# Green_Light_Check.net
KiCad netlist of a schematic drawn in Altium Designer
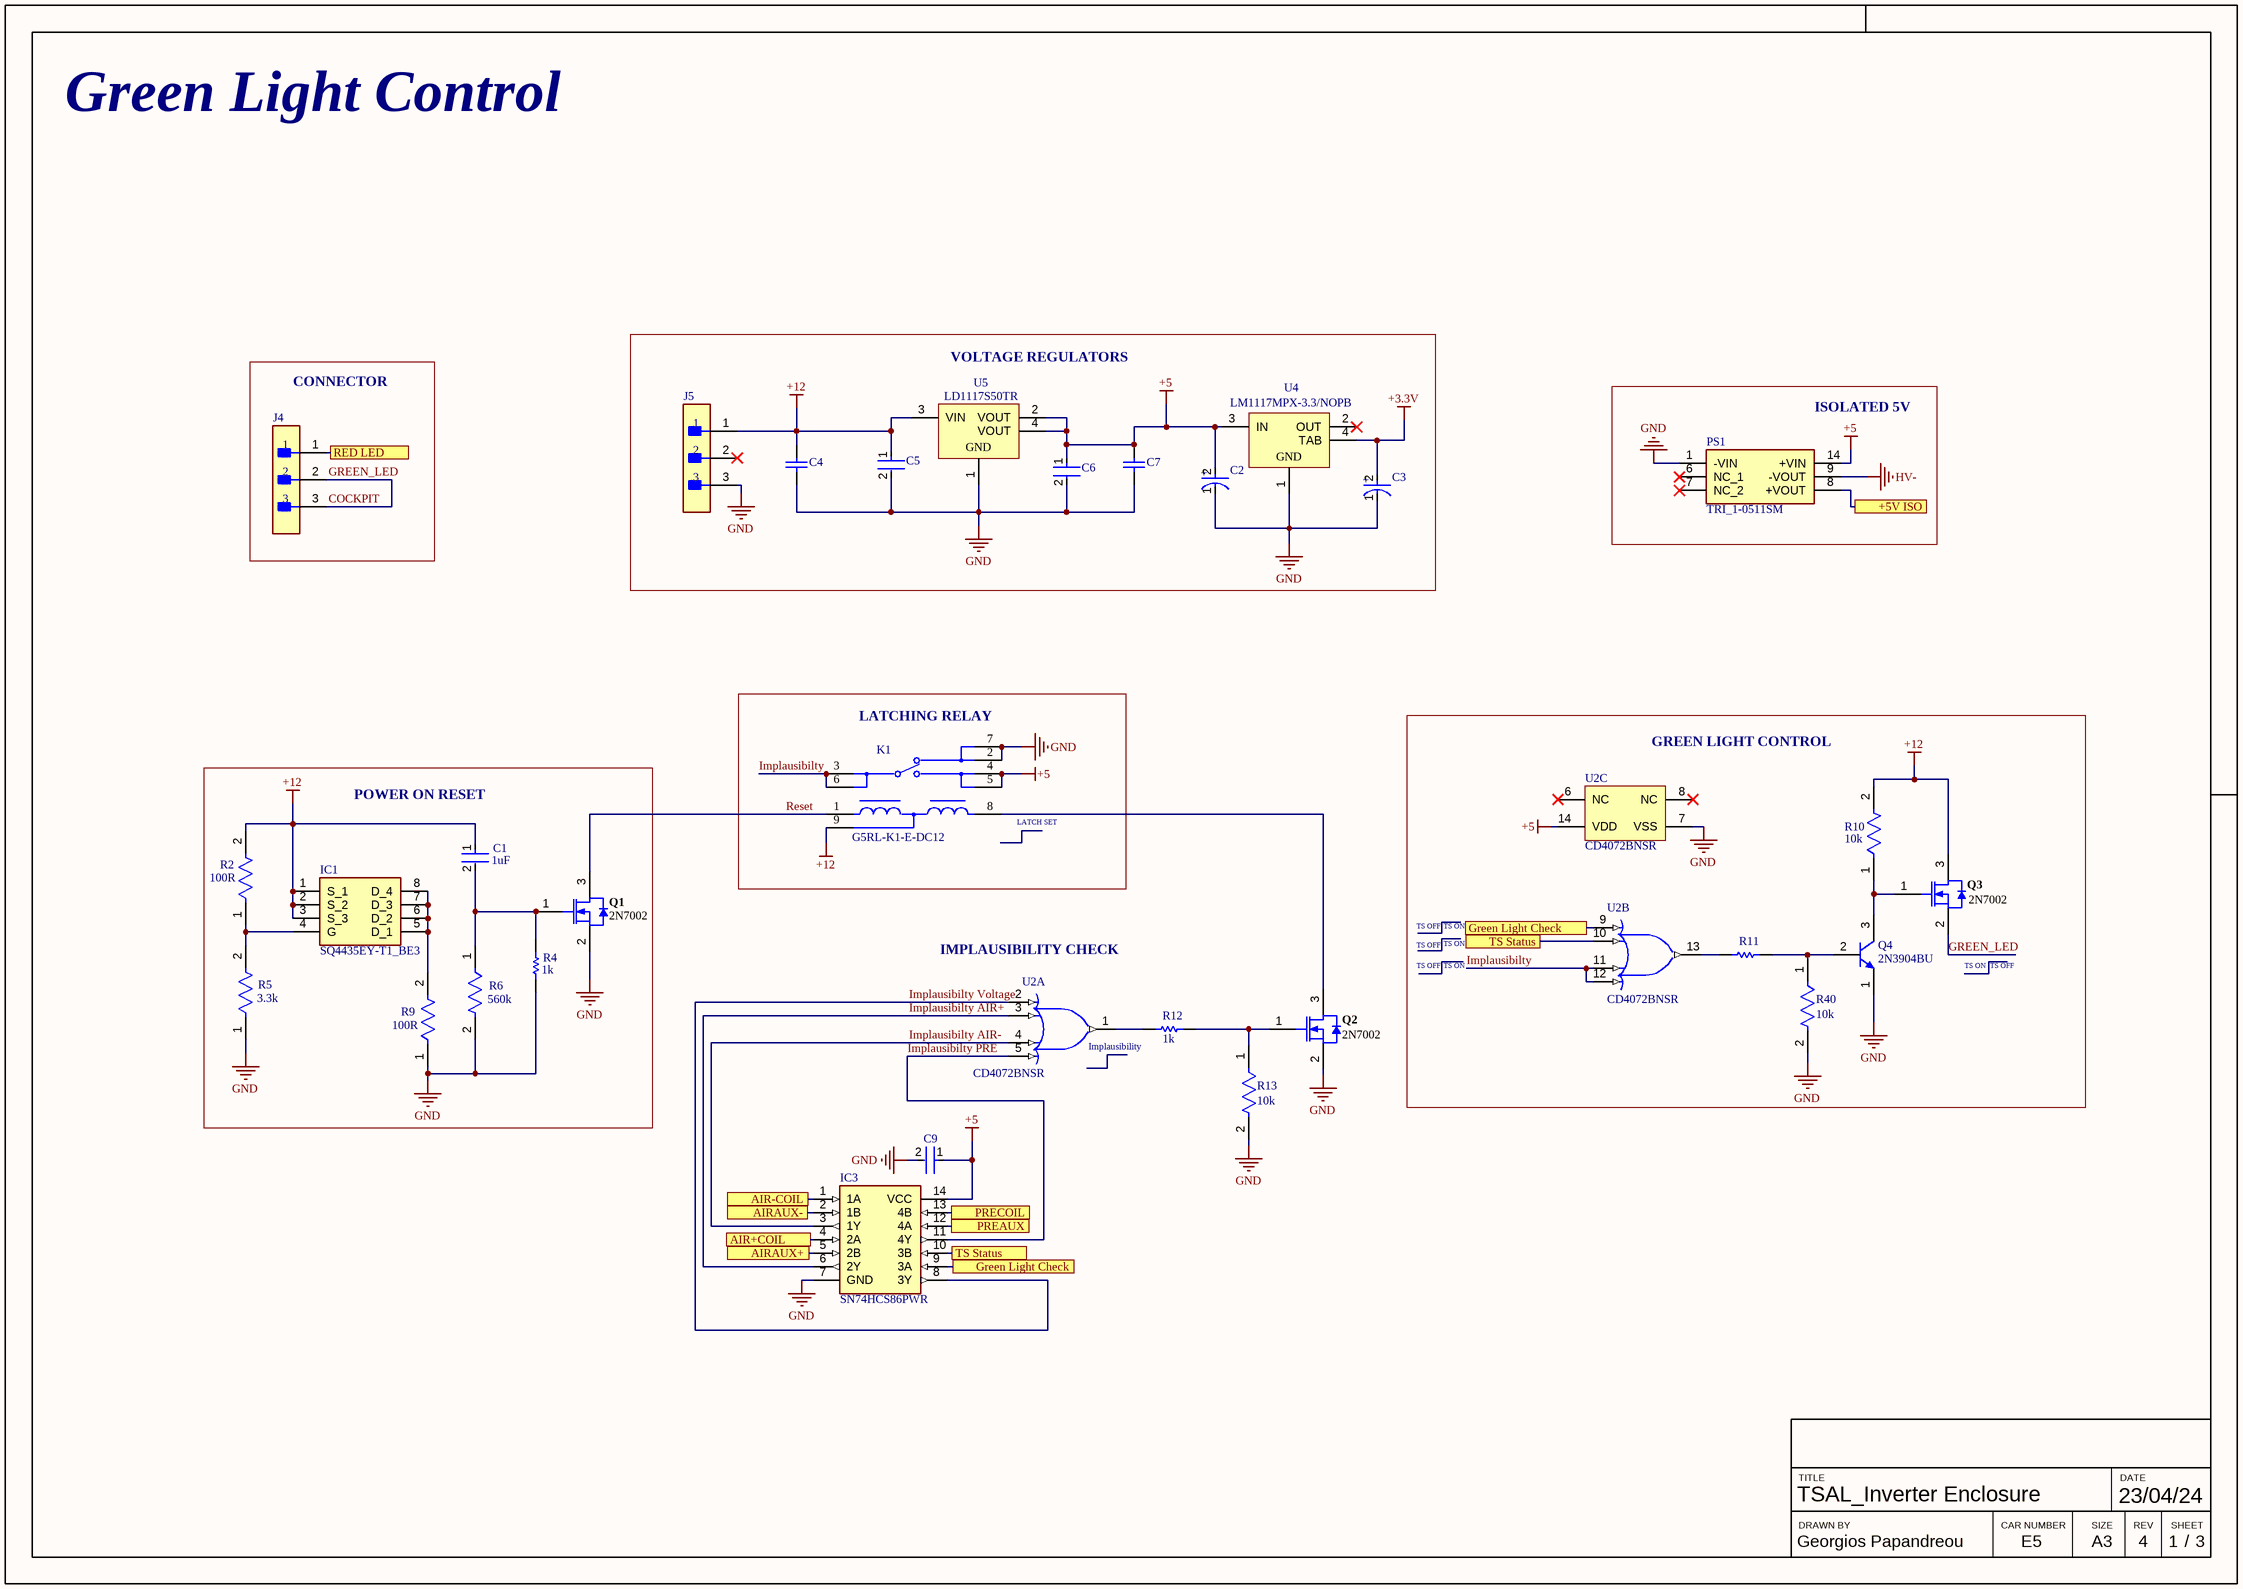
[diagram p0: Green_Light_Check.SchDoc]

(export (version "E")
  (design (tool "Eeschema 10.0.6"))
  (components
    (comp (ref "C1")
      (value "CGA5L2X7R1E105K160AA")
      (footprint "FP-CGA5L-0_3-0_1-MFG")
      (description "Cap Ceramic 1uF 25V X7R 10% Pad SMD 1206 +125°C Automotive T/R")
      (fields (field (name "TOLERANCE") "10%"))
      (libsource (lib "Altium Content Vault") (part "b4654b650e69147ec39a6b967a45e02"))
    )
    (comp (ref "C2")
      (value "TAJP106M010RNJ")
      (footprint "FP-TAJP-MFG")
      (description "10uF 10V  ±20% 6Ω 0805  SMD Tantalum Capacitor")
      (fields (field (name "TOLERANCE") "20%") (field (name "VOLTAGE") "10V"))
      (libsource (lib "Altium Content Vault") (part "a00bbbee19879c290e62620ae7e47b1"))
    )
    (comp (ref "C3")
      (value "TAJP106M010RNJ")
      (footprint "FP-TAJP-MFG")
      (description "10uF 10V  ±20% 6Ω 0805  SMD Tantalum Capacitor")
      (fields (field (name "TOLERANCE") "20%") (field (name "VOLTAGE") "10V"))
      (libsource (lib "Altium Content Vault") (part "a00bbbee19879c290e62620ae7e47b1"))
    )
    (comp (ref "C4")
      (value "C1206C106K8RACTU")
      (footprint "CAPC3216X180X50LL20T25")
      (description "Chip Capacitor, 10 uF, +/- 10%, 10 V, -55 to 125 degC, 1206 (3216 Metric), RoHS, Tape and Reel")
      (fields (field (name "TOLERANCE") "10%") (field (name "MANUFACTURER") "Kemet"))
      (libsource (lib "Altium Content Vault") (part "CAP-NP-2"))
    )
    (comp (ref "C5")
      (value "CL21B104KBCNNNC")
      (footprint "FP-CL21-IPC_C")
      (description "CL21 Series 0805 100nF 50V ±10% Tolerance X7R Multilayer Ceramic Chip Capacitor")
      (fields (field (name "TOLERANCE") "10%") (field (name "VOLTAGE") "50V"))
      (libsource (lib "Altium Content Vault") (part "b4654b650e69147ec39a6b967a45e02"))
    )
    (comp (ref "C6")
      (value "CL21B104KBCNNNC")
      (footprint "FP-CL21-IPC_C")
      (description "CL21 Series 0805 100nF 50V ±10% Tolerance X7R Multilayer Ceramic Chip Capacitor")
      (fields (field (name "TOLERANCE") "10%") (field (name "VOLTAGE") "50V"))
      (libsource (lib "Altium Content Vault") (part "b4654b650e69147ec39a6b967a45e02"))
    )
    (comp (ref "C7")
      (value "C1206C106K8RACTU")
      (footprint "CAPC3216X180X50LL20T25")
      (description "Chip Capacitor, 10 uF, +/- 10%, 10 V, -55 to 125 degC, 1206 (3216 Metric), RoHS, Tape and Reel")
      (fields (field (name "TOLERANCE") "10%") (field (name "MANUFACTURER") "Kemet"))
      (libsource (lib "Altium Content Vault") (part "CAP-NP-2"))
    )
    (comp (ref "C9")
      (value "CL21B104KBCNNNC")
      (footprint "FP-CL21-IPC_C")
      (description "CL21 Series 0805 100nF 50V ±10% Tolerance X7R Multilayer Ceramic Chip Capacitor")
      (fields (field (name "TOLERANCE") "10%") (field (name "VOLTAGE") "50V"))
      (libsource (lib "Altium Content Vault") (part "b4654b650e69147ec39a6b967a45e02"))
    )
    (comp (ref "IC1")
      (value "SQ4435EY-T1_BE3")
      (footprint "SamacSys:SOIC127P600X175-8N")
      (description "Integrated Circuit")
      (fields (field (name "MOUSER PART NUMBER") "78-SQ4435EY-T1_BE3"))
      (libsource (lib "*") (part "SQ4435EY-T1_BE3"))
    )
    (comp (ref "IC3")
      (value "SN74HCS86PWR")
      (footprint "SamacSys:SOP65P640X120-14N")
      (description "Integrated Circuit")
      (fields (field (name "MOUSER PART NUMBER") "595-SN74HCS86PWR"))
      (libsource (lib "*") (part "SN74HCS86PWR"))
    )
    (comp (ref "J4")
      (value "22-04-1031")
      (footprint "FP-22-04-1031-MFG")
      (description "CONN HEADER VERT 3POS 2.5MM")
      (libsource (lib "Altium Content Vault") (part "0d3f023dd272f625e17a2be33dea85f"))
    )
    (comp (ref "J5")
      (value "22-04-1031")
      (footprint "FP-22-04-1031-MFG")
      (description "CONN HEADER VERT 3POS 2.5MM")
      (libsource (lib "Altium Content Vault") (part "0d3f023dd272f625e17a2be33dea85f"))
    )
    (comp (ref "K1")
      (value "G5RL-K1-E-DC12")
      (footprint "FP-G5RL-K1-E-DC12-MFG")
      (description "RELAY GEN PURPOSE SPDT 16A 12V")
      (libsource (lib "Altium Content Vault") (part "7d82a989438c6ed582eab30b2709a09"))
    )
    (comp (ref "PS1")
      (value "TRI_1-0511SM")
      (footprint "SamacSys:TRI10511SM")
      (description "Power Supply")
      (fields (field (name "MANUFACTURER_PART_NUMBER") "TRI 1-0511SM"))
      (libsource (lib "*") (part "TRI_1-0511SM"))
    )
    (comp (ref "Q1")
      (value "2N7002")
      (footprint "INF-PG-SOT23_M")
      (fields (field (name "MANUFACTURER") "Infineon"))
      (libsource (lib "Altium Content Vault") (part "INF-NDMOS-GSD-3"))
    )
    (comp (ref "Q2")
      (value "2N7002")
      (footprint "INF-PG-SOT23_M")
      (fields (field (name "MANUFACTURER") "Infineon"))
      (libsource (lib "Altium Content Vault") (part "INF-NDMOS-GSD-3"))
    )
    (comp (ref "Q3")
      (value "2N7002")
      (footprint "INF-PG-SOT23_M")
      (fields (field (name "MANUFACTURER") "Infineon"))
      (libsource (lib "Altium Content Vault") (part "INF-NDMOS-GSD-3"))
    )
    (comp (ref "Q4")
      (value "2N3904BU")
      (footprint "FAIR-TO-92")
      (description "NPN General-Purpose Amplifier, 40 V VCEO, 0.2 A, -55 to 150 degC, 2-Pin TO-92, RoHS, Bulk")
      (fields (field (name "MANUFACTURER") "FairchildSemiconductor"))
      (libsource (lib "Altium Content Vault") (part "NPN-E1B2C3-3"))
    )
    (comp (ref "R2")
      (value "CRCW1206100RFKEA")
      (footprint "FP-CRCW1206-e3-MFG")
      (description "RES Thick Film, 100Ω, 1%, 0.25W, 100ppm/°C, 1206")
      (fields (field (name "TOLERANCE") "1%"))
      (libsource (lib "Altium Content Vault") (part "1029c3af85768c4190bb7ad29bc67b5"))
    )
    (comp (ref "R4")
      (value "1K 1% 1206(3216)")
      (footprint "RESC1206(3216)_N")
      (description "1K 0.25W 1% 1206 (3216 Metric)  SMD")
      (fields (field (name "POWER") "0.25 W") (field (name "TOLERANCE") "1 %"))
      (libsource (lib "Altium Content Vault") (part "RES"))
    )
    (comp (ref "R5")
      (value "CRCW12063K30FKEB")
      (footprint "FP-CRCW1206-e3-IPC_B")
      (description "RES Thick Film, 3.3kΩ, 1%, 0.25W, 100ppm/°C, 1206")
      (fields (field (name "TOLERANCE") "1%"))
      (libsource (lib "Altium Content Vault") (part "1029c3af85768c4190bb7ad29bc67b5"))
    )
    (comp (ref "R6")
      (value "RT1206BRD07560KL")
      (footprint "FP-RT1206-MFG")
      (description "RES SMD 560K OHM 0.1% 1/4W 1206")
      (fields (field (name "MANUFACTURER") "Yageo") (field (name "TOLERANCE") "0.005"))
      (libsource (lib "Altium Content Vault") (part "1029c3af85768c4190bb7ad29bc67b5"))
    )
    (comp (ref "R9")
      (value "CRCW1206100RFKEA")
      (footprint "FP-CRCW1206-e3-MFG")
      (description "RES Thick Film, 100Ω, 1%, 0.25W, 100ppm/°C, 1206")
      (fields (field (name "TOLERANCE") "1%"))
      (libsource (lib "Altium Content Vault") (part "1029c3af85768c4190bb7ad29bc67b5"))
    )
    (comp (ref "R10")
      (value "CRCW120610K0FKEA")
      (footprint "FP-CRCW1206-e3-IPC_C")
      (description "RES Thick Film, 10kΩ, 1%, 0.25W, 100ppm/°C, 1206")
      (fields (field (name "TOLERANCE") "1%"))
      (libsource (lib "Altium Content Vault") (part "1029c3af85768c4190bb7ad29bc67b5"))
    )
    (comp (ref "R11")
      (value "RK73B2ATTD102J")
      (footprint "RESC2013X60X30ML20T20")
      (fields (field (name "MANUFACTURER") "KOA Speer"))
      (libsource (lib "Altium Content Vault") (part "RES"))
    )
    (comp (ref "R12")
      (value "RK73B2ATTD102J")
      (footprint "RESC2013X60X30ML20T20")
      (fields (field (name "MANUFACTURER") "KOA Speer"))
      (libsource (lib "Altium Content Vault") (part "RES"))
    )
    (comp (ref "R13")
      (value "CRCW120610K0FKEA")
      (footprint "FP-CRCW1206-e3-IPC_C")
      (description "RES Thick Film, 10kΩ, 1%, 0.25W, 100ppm/°C, 1206")
      (fields (field (name "TOLERANCE") "1%"))
      (libsource (lib "Altium Content Vault") (part "1029c3af85768c4190bb7ad29bc67b5"))
    )
    (comp (ref "R40")
      (value "CRCW120610K0FKEA")
      (footprint "FP-CRCW1206-e3-IPC_C")
      (description "RES Thick Film, 10kΩ, 1%, 0.25W, 100ppm/°C, 1206")
      (fields (field (name "TOLERANCE") "1%"))
      (libsource (lib "Altium Content Vault") (part "1029c3af85768c4190bb7ad29bc67b5"))
    )
    (comp (ref "U2")
      (value "CD4072BNSR")
      (footprint "NS0014A_M")
      (description "CMOS Dual 4-Input OR Gate, NS0014A, LARGE T&R")
      (fields
        (field (name "MANUFACTURER") "Texas Instruments")
        (field (name "GENERIC PART NUMBER") "CD4072B")
      )
      (libsource (lib "Altium Content Vault") (part "TI-CD4072B-14"))
    )
    (comp (ref "U4")
      (value "LM1117MPX-3.3/NOPB")
      (footprint "DCY0004A_L")
      (description "800mA Low-Dropout Linear Regulator, 4-pin SOT-223, Pb-Free")
      (fields (field (name "MANUFACTURER") "Texas Instruments"))
      (libsource (lib "Altium Content Vault") (part "PM-REG-LM1086-SOT4"))
    )
    (comp (ref "U5")
      (value "LD1117S50TR")
      (footprint "SOT-223_L")
      (description "Fixed Low Drop Positive Voltage Regulator, 5V, 4-Pin SOT-223, Tape and Reel")
      (libsource (lib "Altium Content Vault") (part "PM-REG-LD1117-SOT4"))
    )
  )
  (nets
    (net (code "1") (name "+3.3V") (class "Default")
      (node (ref "C3") (pin "2") (pinfunction "A_2") (pintype "passive"))
      (node (ref "U4") (pin "4") (pinfunction "TAB_4") (pintype "power_in"))
    )
    (net (code "2") (name "+5") (class "Default")
      (node (ref "C2") (pin "2") (pinfunction "A_2") (pintype "passive"))
      (node (ref "C6") (pin "1") (pinfunction "1_1") (pintype "passive"))
      (node (ref "C7") (pin "2") (pinfunction "2_2") (pintype "passive"))
      (node (ref "C9") (pin "1") (pinfunction "1_1") (pintype "passive"))
      (node (ref "IC3") (pin "14") (pinfunction "VCC_14") (pintype "power_in"))
      (node (ref "K1") (pin "4") (pinfunction "4_4") (pintype "passive"))
      (node (ref "K1") (pin "5") (pinfunction "5_5") (pintype "passive"))
      (node (ref "PS1") (pin "14") (pinfunction "+VIN_14") (pintype "passive"))
      (node (ref "U2") (pin "14") (pinfunction "VDD_14") (pintype "power_in"))
      (node (ref "U4") (pin "3") (pinfunction "IN_3") (pintype "power_in"))
      (node (ref "U5") (pin "2") (pinfunction "VOUT_2") (pintype "power_in"))
      (node (ref "U5") (pin "4") (pinfunction "VOUT_4") (pintype "power_in"))
    )
    (net (code "3") (name "+12") (class "Default")
      (node (ref "C1") (pin "1") (pinfunction "1_1") (pintype "passive"))
      (node (ref "C4") (pin "2") (pinfunction "2_2") (pintype "passive"))
      (node (ref "C5") (pin "1") (pinfunction "1_1") (pintype "passive"))
      (node (ref "IC1") (pin "1") (pinfunction "S_1_1") (pintype "passive"))
      (node (ref "IC1") (pin "2") (pinfunction "S_2_2") (pintype "passive"))
      (node (ref "IC1") (pin "3") (pinfunction "S_3_3") (pintype "passive"))
      (node (ref "J5") (pin "1") (pinfunction "1_1") (pintype "passive"))
      (node (ref "K1") (pin "9") (pinfunction "S+/R+_9") (pintype "passive"))
      (node (ref "Q3") (pin "3") (pinfunction "DRAIN_3") (pintype "passive"))
      (node (ref "R10") (pin "2") (pinfunction "2_2") (pintype "passive"))
      (node (ref "R2") (pin "2") (pinfunction "2_2") (pintype "passive"))
      (node (ref "U5") (pin "3") (pinfunction "VIN_3") (pintype "power_in"))
    )
    (net (code "4") (name "/+5V ISO") (class "Default")
      (node (ref "PS1") (pin "8") (pinfunction "+VOUT_8") (pintype "passive"))
    )
    (net (code "5") (name "/AIR+COIL") (class "Default")
      (node (ref "IC3") (pin "4") (pinfunction "2A_4") (pintype "input"))
    )
    (net (code "6") (name "/AIR-COIL") (class "Default")
      (node (ref "IC3") (pin "1") (pinfunction "1A_1") (pintype "input"))
    )
    (net (code "7") (name "/AIRAUX+") (class "Default")
      (node (ref "IC3") (pin "5") (pinfunction "2B_5") (pintype "input"))
    )
    (net (code "8") (name "/AIRAUX-") (class "Default")
      (node (ref "IC3") (pin "2") (pinfunction "1B_2") (pintype "input"))
    )
    (net (code "9") (name "/COCKPIT") (class "Default")
      (node (ref "J4") (pin "2") (pinfunction "2_2") (pintype "passive"))
      (node (ref "J4") (pin "3") (pinfunction "3_3") (pintype "passive"))
      (node (ref "Q3") (pin "2") (pinfunction "SOURCE_2") (pintype "passive"))
    )
    (net (code "10") (name "/Green Light Check") (class "Default")
      (node (ref "IC3") (pin "9") (pinfunction "3A_9") (pintype "input"))
      (node (ref "U2") (pin "9") (pinfunction "E_9") (pintype "input"))
    )
    (net (code "11") (name "/Implausibilty") (class "Default")
      (node (ref "K1") (pin "3") (pinfunction "3_3") (pintype "passive"))
      (node (ref "K1") (pin "6") (pinfunction "6_6") (pintype "passive"))
      (node (ref "U2") (pin "11") (pinfunction "G_11") (pintype "input"))
      (node (ref "U2") (pin "12") (pinfunction "H_12") (pintype "input"))
    )
    (net (code "12") (name "/Implausibilty AIR+") (class "Default")
      (node (ref "IC3") (pin "6") (pinfunction "2Y_6") (pintype "output"))
      (node (ref "U2") (pin "3") (pinfunction "B_3") (pintype "input"))
    )
    (net (code "13") (name "/Implausibilty AIR-") (class "Default")
      (node (ref "IC3") (pin "3") (pinfunction "1Y_3") (pintype "output"))
      (node (ref "U2") (pin "4") (pinfunction "C_4") (pintype "input"))
    )
    (net (code "14") (name "/Implausibilty PRE") (class "Default")
      (node (ref "IC3") (pin "11") (pinfunction "4Y_11") (pintype "output"))
      (node (ref "U2") (pin "5") (pinfunction "D_5") (pintype "input"))
    )
    (net (code "15") (name "/Implausibilty Voltage") (class "Default")
      (node (ref "IC3") (pin "8") (pinfunction "3Y_8") (pintype "output"))
      (node (ref "U2") (pin "2") (pinfunction "A_2") (pintype "input"))
    )
    (net (code "16") (name "/PREAUX") (class "Default")
      (node (ref "IC3") (pin "12") (pinfunction "4A_12") (pintype "input"))
    )
    (net (code "17") (name "/PRECOIL") (class "Default")
      (node (ref "IC3") (pin "13") (pinfunction "4B_13") (pintype "input"))
    )
    (net (code "18") (name "/RED LED") (class "Default")
      (node (ref "J4") (pin "1") (pinfunction "1_1") (pintype "passive"))
    )
    (net (code "19") (name "/Reset") (class "Default")
      (node (ref "K1") (pin "1") (pinfunction "R-_1") (pintype "passive"))
      (node (ref "Q1") (pin "3") (pinfunction "DRAIN_3") (pintype "passive"))
    )
    (net (code "20") (name "/TS Status") (class "Default")
      (node (ref "IC3") (pin "10") (pinfunction "3B_10") (pintype "input"))
      (node (ref "U2") (pin "10") (pinfunction "F_10") (pintype "input"))
    )
    (net (code "21") (name "GND") (class "Default")
      (node (ref "C2") (pin "1") (pinfunction "C_1") (pintype "passive"))
      (node (ref "C3") (pin "1") (pinfunction "C_1") (pintype "passive"))
      (node (ref "C4") (pin "1") (pinfunction "1_1") (pintype "passive"))
      (node (ref "C5") (pin "2") (pinfunction "2_2") (pintype "passive"))
      (node (ref "C6") (pin "2") (pinfunction "2_2") (pintype "passive"))
      (node (ref "C7") (pin "1") (pinfunction "1_1") (pintype "passive"))
      (node (ref "C9") (pin "2") (pinfunction "2_2") (pintype "passive"))
      (node (ref "IC3") (pin "7") (pinfunction "GND_7") (pintype "power_in"))
      (node (ref "J5") (pin "3") (pinfunction "3_3") (pintype "passive"))
      (node (ref "K1") (pin "2") (pinfunction "2_2") (pintype "passive"))
      (node (ref "K1") (pin "7") (pinfunction "7_7") (pintype "passive"))
      (node (ref "PS1") (pin "1") (pinfunction "-VIN_1") (pintype "passive"))
      (node (ref "Q1") (pin "2") (pinfunction "SOURCE_2") (pintype "passive"))
      (node (ref "Q2") (pin "2") (pinfunction "SOURCE_2") (pintype "passive"))
      (node (ref "Q4") (pin "1") (pinfunction "E_1") (pintype "passive"))
      (node (ref "R13") (pin "2") (pinfunction "2_2") (pintype "passive"))
      (node (ref "R4") (pin "1") (pinfunction "1_1") (pintype "passive"))
      (node (ref "R40") (pin "2") (pinfunction "2_2") (pintype "passive"))
      (node (ref "R5") (pin "1") (pinfunction "1_1") (pintype "passive"))
      (node (ref "R6") (pin "2") (pinfunction "2_2") (pintype "passive"))
      (node (ref "R9") (pin "1") (pinfunction "1_1") (pintype "passive"))
      (node (ref "U2") (pin "7") (pinfunction "VSS_7") (pintype "power_in"))
      (node (ref "U4") (pin "1") (pinfunction "GND_1") (pintype "power_in"))
      (node (ref "U5") (pin "1") (pinfunction "GND_1") (pintype "power_in"))
    )
    (net (code "22") (name "HV-") (class "Default")
      (node (ref "PS1") (pin "9") (pinfunction "-VOUT_9") (pintype "passive"))
    )
    (net (code "23") (name "Net-(IC1-D_1)") (class "Default")
      (node (ref "IC1") (pin "5") (pinfunction "D_1_5") (pintype "passive"))
      (node (ref "IC1") (pin "6") (pinfunction "D_2_6") (pintype "passive"))
      (node (ref "IC1") (pin "7") (pinfunction "D_3_7") (pintype "passive"))
      (node (ref "IC1") (pin "8") (pinfunction "D_4_8") (pintype "passive"))
      (node (ref "R9") (pin "2") (pinfunction "2_2") (pintype "passive"))
    )
    (net (code "24") (name "Net-(IC1-G)") (class "Default")
      (node (ref "IC1") (pin "4") (pinfunction "G_4") (pintype "passive"))
      (node (ref "R2") (pin "1") (pinfunction "1_1") (pintype "passive"))
      (node (ref "R5") (pin "2") (pinfunction "2_2") (pintype "passive"))
    )
    (net (code "25") (name "Net-(K1-S-)") (class "Default")
      (node (ref "K1") (pin "8") (pinfunction "S-_8") (pintype "passive"))
      (node (ref "Q2") (pin "3") (pinfunction "DRAIN_3") (pintype "passive"))
    )
    (net (code "26") (name "Net-(Q1-GATE)") (class "Default")
      (node (ref "C1") (pin "2") (pinfunction "2_2") (pintype "passive"))
      (node (ref "Q1") (pin "1") (pinfunction "GATE_1") (pintype "passive"))
      (node (ref "R4") (pin "2") (pinfunction "2_2") (pintype "passive"))
      (node (ref "R6") (pin "1") (pinfunction "1_1") (pintype "passive"))
    )
    (net (code "27") (name "Net-(Q2-GATE)") (class "Default")
      (node (ref "Q2") (pin "1") (pinfunction "GATE_1") (pintype "passive"))
      (node (ref "R12") (pin "2") (pinfunction "2_2") (pintype "passive"))
      (node (ref "R13") (pin "1") (pinfunction "1_1") (pintype "passive"))
    )
    (net (code "28") (name "Net-(Q3-GATE)") (class "Default")
      (node (ref "Q3") (pin "1") (pinfunction "GATE_1") (pintype "passive"))
      (node (ref "Q4") (pin "3") (pinfunction "C_3") (pintype "passive"))
      (node (ref "R10") (pin "1") (pinfunction "1_1") (pintype "passive"))
    )
    (net (code "29") (name "Net-(Q4-B)") (class "Default")
      (node (ref "Q4") (pin "2") (pinfunction "B_2") (pintype "passive"))
      (node (ref "R11") (pin "2") (pinfunction "2_2") (pintype "passive"))
      (node (ref "R40") (pin "1") (pinfunction "1_1") (pintype "passive"))
    )
    (net (code "30") (name "Net-(U2A-J)") (class "Default")
      (node (ref "R12") (pin "1") (pinfunction "1_1") (pintype "passive"))
      (node (ref "U2") (pin "1") (pinfunction "J_1") (pintype "output"))
    )
    (net (code "31") (name "Net-(U2B-K)") (class "Default")
      (node (ref "R11") (pin "1") (pinfunction "1_1") (pintype "passive"))
      (node (ref "U2") (pin "13") (pinfunction "K_13") (pintype "output"))
    )
    (net (code "32") (name "unconnected-(J5-Pad2)") (class "Default")
      (node (ref "J5") (pin "2") (pinfunction "2_2") (pintype "passive+no_connect"))
    )
    (net (code "33") (name "unconnected-(PS1-NC_1-Pad6)") (class "Default")
      (node (ref "PS1") (pin "6") (pinfunction "NC_1_6") (pintype "passive+no_connect"))
    )
    (net (code "34") (name "unconnected-(PS1-NC_2-Pad7)") (class "Default")
      (node (ref "PS1") (pin "7") (pinfunction "NC_2_7") (pintype "passive+no_connect"))
    )
    (net (code "35") (name "unconnected-(U2C-NC-Pad6)") (class "Default")
      (node (ref "U2") (pin "6") (pinfunction "NC_6") (pintype "passive+no_connect"))
    )
    (net (code "36") (name "unconnected-(U2C-NC-Pad8)") (class "Default")
      (node (ref "U2") (pin "8") (pinfunction "NC_8") (pintype "passive+no_connect"))
    )
    (net (code "37") (name "unconnected-(U4-OUT-Pad2)") (class "Default")
      (node (ref "U4") (pin "2") (pinfunction "OUT_2") (pintype "power_in+no_connect"))
    )
  )
)
